# InitialTransceivers.net
KiCad netlist of a schematic drawn in EAGLE
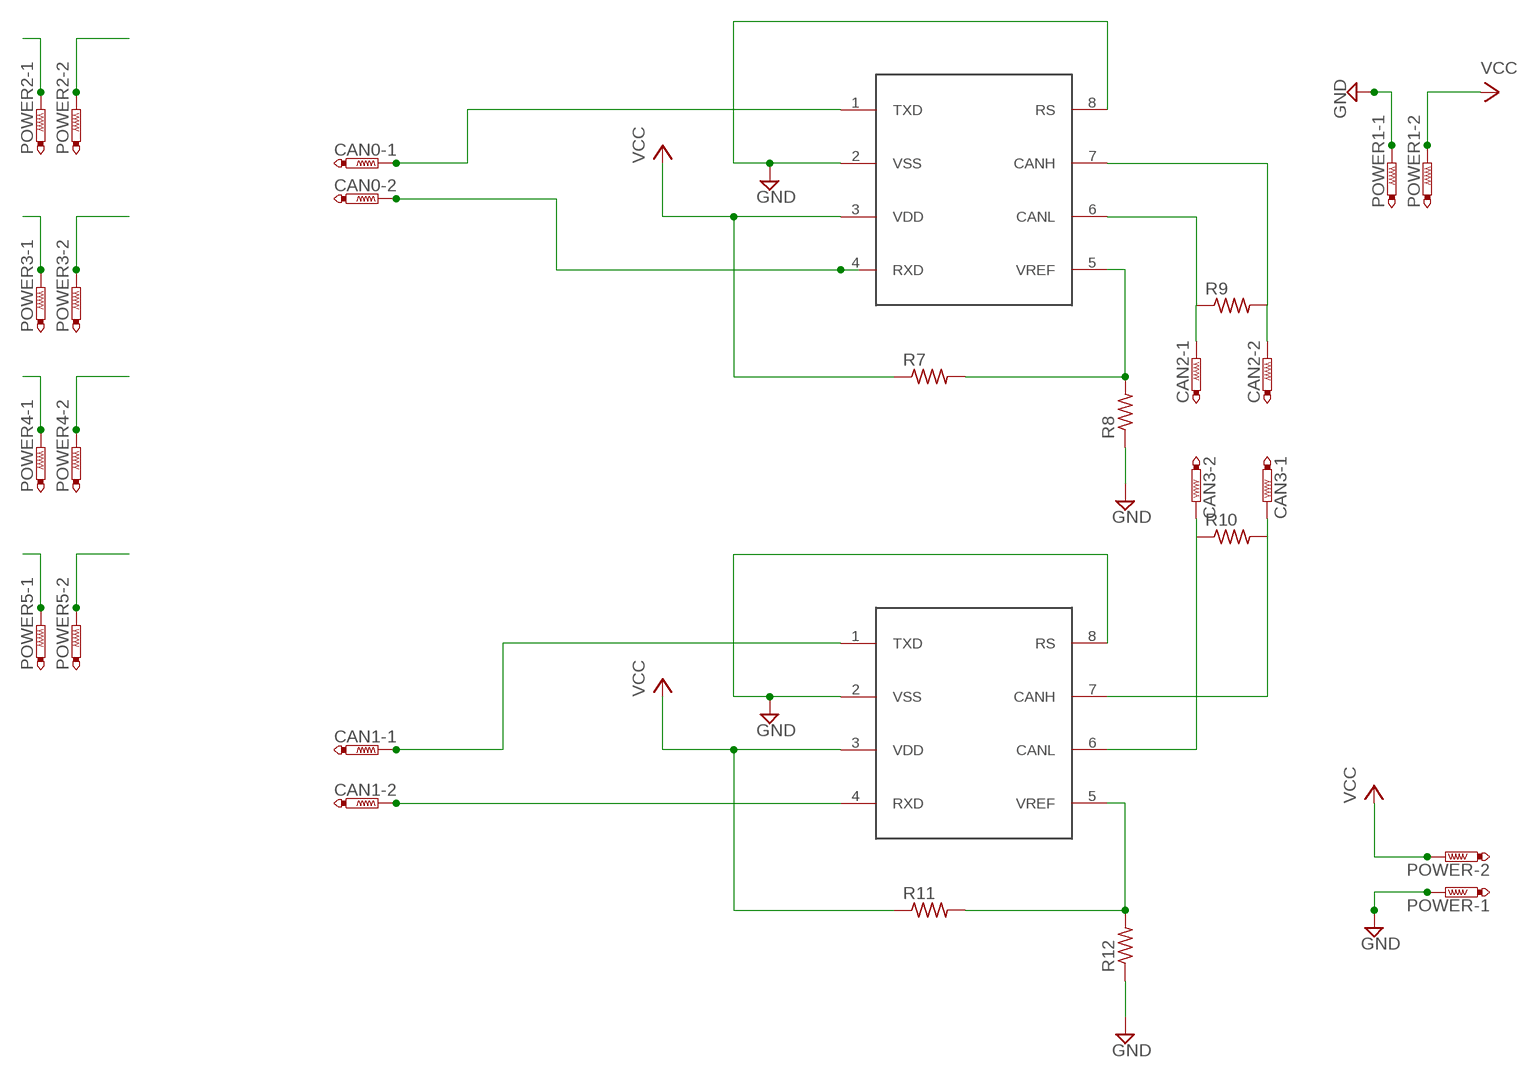
[diagram p0: schematic, sheet 1]

(export (version "E")
  (design (tool "Eeschema 10.0.6"))
  (components
    (comp (ref "CAN0")
      (value "PTR2")
      (footprint "eagle-import:P2-38-17")
      (libsource (lib "eagle-import") (part "PTR2"))
    )
    (comp (ref "CAN1")
      (value "PTR2")
      (footprint "eagle-import:P2-38-17")
      (libsource (lib "eagle-import") (part "PTR2"))
    )
    (comp (ref "CAN2")
      (value "PTR2")
      (footprint "eagle-import:P2-38-17")
      (libsource (lib "eagle-import") (part "PTR2"))
    )
    (comp (ref "CAN3")
      (value "PTR2")
      (footprint "eagle-import:P2-38-17")
      (libsource (lib "eagle-import") (part "PTR2"))
    )
    (comp (ref "POWER")
      (value "PTR2")
      (footprint "eagle-import:P2-38-17")
      (libsource (lib "eagle-import") (part "PTR2"))
    )
    (comp (ref "POWER1")
      (value "PTR2")
      (footprint "eagle-import:P2-38-17")
      (libsource (lib "eagle-import") (part "PTR2"))
    )
    (comp (ref "POWER2")
      (value "PTR2")
      (footprint "eagle-import:P2-38-17")
      (libsource (lib "eagle-import") (part "PTR2"))
    )
    (comp (ref "POWER3")
      (value "PTR2")
      (footprint "eagle-import:P2-38-17")
      (libsource (lib "eagle-import") (part "PTR2"))
    )
    (comp (ref "POWER4")
      (value "PTR2")
      (footprint "eagle-import:P2-38-17")
      (libsource (lib "eagle-import") (part "PTR2"))
    )
    (comp (ref "POWER5")
      (value "PTR2")
      (footprint "eagle-import:P2-38-17")
      (libsource (lib "eagle-import") (part "PTR2"))
    )
    (comp (ref "R7")
      (value "R-US_0204/5")
      (footprint "eagle-import:0204_5")
      (libsource (lib "eagle-import") (part "R-US_0204/5"))
    )
    (comp (ref "R8")
      (value "R-US_0204/5")
      (footprint "eagle-import:0204_5")
      (libsource (lib "eagle-import") (part "R-US_0204/5"))
    )
    (comp (ref "R9")
      (value "R-US_0204/5")
      (footprint "eagle-import:0204_5")
      (libsource (lib "eagle-import") (part "R-US_0204/5"))
    )
    (comp (ref "R10")
      (value "R-US_0204/5")
      (footprint "eagle-import:0204_5")
      (libsource (lib "eagle-import") (part "R-US_0204/5"))
    )
    (comp (ref "R11")
      (value "R-US_0204/5")
      (footprint "eagle-import:0204_5")
      (libsource (lib "eagle-import") (part "R-US_0204/5"))
    )
    (comp (ref "R12")
      (value "R-US_0204/5")
      (footprint "eagle-import:0204_5")
      (libsource (lib "eagle-import") (part "R-US_0204/5"))
    )
    (comp (ref "U$2")
      (value "MCP2551-DIP")
      (footprint "eagle-import:DIL08")
      (libsource (lib "eagle-import") (part "MCP2551-DIP"))
    )
    (comp (ref "U$3")
      (value "MCP2551-DIP")
      (footprint "eagle-import:DIL08")
      (libsource (lib "eagle-import") (part "MCP2551-DIP"))
    )
  )
  (nets
    (net (code "1") (name "/A0") (class "Default")
      (node (ref "POWER2") (pin "TP-1") (pinfunction "TP_TP-1") (pintype "input"))
      (node (ref "POWER3") (pin "TP-1") (pinfunction "TP_TP-1") (pintype "input"))
    )
    (net (code "2") (name "/A1") (class "Default")
      (node (ref "POWER2") (pin "TP-2") (pinfunction "TP_TP-2") (pintype "input"))
      (node (ref "POWER3") (pin "TP-2") (pinfunction "TP_TP-2") (pintype "input"))
    )
    (net (code "3") (name "/A2") (class "Default")
      (node (ref "POWER4") (pin "TP-1") (pinfunction "TP_TP-1") (pintype "input"))
      (node (ref "POWER5") (pin "TP-1") (pinfunction "TP_TP-1") (pintype "input"))
    )
    (net (code "4") (name "/A3") (class "Default")
      (node (ref "POWER4") (pin "TP-2") (pinfunction "TP_TP-2") (pintype "input"))
      (node (ref "POWER5") (pin "TP-2") (pinfunction "TP_TP-2") (pintype "input"))
    )
    (net (code "5") (name "GND") (class "Default")
      (node (ref "POWER") (pin "TP-1") (pinfunction "TP_TP-1") (pintype "input"))
      (node (ref "POWER1") (pin "TP-1") (pinfunction "TP_TP-1") (pintype "input"))
      (node (ref "R12") (pin "1") (pinfunction "1_1") (pintype "passive"))
      (node (ref "R8") (pin "1") (pinfunction "1_1") (pintype "passive"))
      (node (ref "U$2") (pin "2") (pinfunction "VSS_2") (pintype "bidirectional"))
      (node (ref "U$2") (pin "8") (pinfunction "RS_8") (pintype "bidirectional"))
      (node (ref "U$3") (pin "2") (pinfunction "VSS_2") (pintype "bidirectional"))
      (node (ref "U$3") (pin "8") (pinfunction "RS_8") (pintype "bidirectional"))
    )
    (net (code "6") (name "Net-(CAN0A-TP)") (class "Default")
      (node (ref "CAN0") (pin "TP-1") (pinfunction "TP_TP-1") (pintype "input"))
      (node (ref "U$2") (pin "1") (pinfunction "TXD_1") (pintype "bidirectional"))
    )
    (net (code "7") (name "Net-(CAN0B-TP)") (class "Default")
      (node (ref "CAN0") (pin "TP-2") (pinfunction "TP_TP-2") (pintype "input"))
      (node (ref "U$2") (pin "4") (pinfunction "RXD_4") (pintype "bidirectional"))
    )
    (net (code "8") (name "Net-(CAN1A-TP)") (class "Default")
      (node (ref "CAN1") (pin "TP-1") (pinfunction "TP_TP-1") (pintype "input"))
      (node (ref "U$3") (pin "1") (pinfunction "TXD_1") (pintype "bidirectional"))
    )
    (net (code "9") (name "Net-(CAN1B-TP)") (class "Default")
      (node (ref "CAN1") (pin "TP-2") (pinfunction "TP_TP-2") (pintype "input"))
      (node (ref "U$3") (pin "4") (pinfunction "RXD_4") (pintype "bidirectional"))
    )
    (net (code "10") (name "Net-(CAN2A-TP)") (class "Default")
      (node (ref "CAN2") (pin "TP-1") (pinfunction "TP_TP-1") (pintype "input"))
      (node (ref "R9") (pin "1") (pinfunction "1_1") (pintype "passive"))
      (node (ref "U$2") (pin "6") (pinfunction "CANL_6") (pintype "bidirectional"))
    )
    (net (code "11") (name "Net-(CAN2B-TP)") (class "Default")
      (node (ref "CAN2") (pin "TP-2") (pinfunction "TP_TP-2") (pintype "input"))
      (node (ref "R9") (pin "2") (pinfunction "2_2") (pintype "passive"))
      (node (ref "U$2") (pin "7") (pinfunction "CANH_7") (pintype "bidirectional"))
    )
    (net (code "12") (name "Net-(CAN3A-TP)") (class "Default")
      (node (ref "CAN3") (pin "TP-1") (pinfunction "TP_TP-1") (pintype "input"))
      (node (ref "R10") (pin "2") (pinfunction "2_2") (pintype "passive"))
      (node (ref "U$3") (pin "7") (pinfunction "CANH_7") (pintype "bidirectional"))
    )
    (net (code "13") (name "Net-(CAN3B-TP)") (class "Default")
      (node (ref "CAN3") (pin "TP-2") (pinfunction "TP_TP-2") (pintype "input"))
      (node (ref "R10") (pin "1") (pinfunction "1_1") (pintype "passive"))
      (node (ref "U$3") (pin "6") (pinfunction "CANL_6") (pintype "bidirectional"))
    )
    (net (code "14") (name "Net-(U$2-VREF)") (class "Default")
      (node (ref "R7") (pin "2") (pinfunction "2_2") (pintype "passive"))
      (node (ref "R8") (pin "2") (pinfunction "2_2") (pintype "passive"))
      (node (ref "U$2") (pin "5") (pinfunction "VREF_5") (pintype "bidirectional"))
    )
    (net (code "15") (name "Net-(U$3-VREF)") (class "Default")
      (node (ref "R11") (pin "2") (pinfunction "2_2") (pintype "passive"))
      (node (ref "R12") (pin "2") (pinfunction "2_2") (pintype "passive"))
      (node (ref "U$3") (pin "5") (pinfunction "VREF_5") (pintype "bidirectional"))
    )
    (net (code "16") (name "VCC") (class "Default")
      (node (ref "POWER") (pin "TP-2") (pinfunction "TP_TP-2") (pintype "input"))
      (node (ref "POWER1") (pin "TP-2") (pinfunction "TP_TP-2") (pintype "input"))
      (node (ref "R11") (pin "1") (pinfunction "1_1") (pintype "passive"))
      (node (ref "R7") (pin "1") (pinfunction "1_1") (pintype "passive"))
      (node (ref "U$2") (pin "3") (pinfunction "VDD_3") (pintype "bidirectional"))
      (node (ref "U$3") (pin "3") (pinfunction "VDD_3") (pintype "bidirectional"))
    )
  )
)
